# SPLIT4.net
KiCad netlist of a schematic drawn in Altium Designer
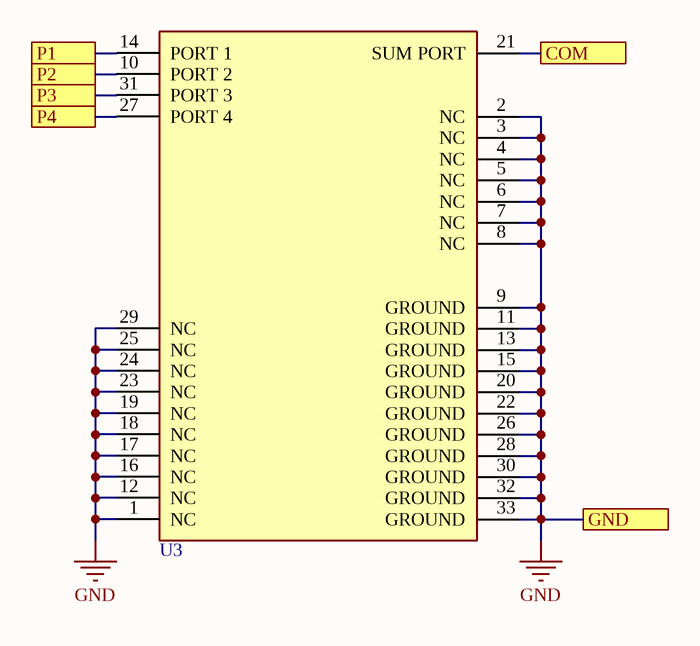
[diagram p0: SPLIT4.SchDoc]

(export (version "E")
  (design (tool "Eeschema 10.0.6"))
  (components
    (comp (ref "U3")
      (value "EP4RKU+")
      (footprint "EP4RKU+")
      (description "Power Splitter/Combiner 4 Way-0° 50Ω DC to 18 GHz")
      (libsource (lib "FullyDigital") (part "EP4RKU+"))
    )
  )
  (nets
    (net (code "1") (name "/COM") (class "Default")
      (node (ref "U3") (pin "21") (pinfunction "SUM_PORT_21") (pintype "passive"))
    )
    (net (code "2") (name "/P1") (class "Default")
      (node (ref "U3") (pin "14") (pinfunction "PORT_1_14") (pintype "passive"))
    )
    (net (code "3") (name "/P2") (class "Default")
      (node (ref "U3") (pin "10") (pinfunction "PORT_2_10") (pintype "passive"))
    )
    (net (code "4") (name "/P3") (class "Default")
      (node (ref "U3") (pin "31") (pinfunction "PORT_3_31") (pintype "passive"))
    )
    (net (code "5") (name "/P4") (class "Default")
      (node (ref "U3") (pin "27") (pinfunction "PORT_4_27") (pintype "passive"))
    )
    (net (code "6") (name "GND") (class "Default")
      (node (ref "U3") (pin "1") (pinfunction "NC_1") (pintype "passive"))
      (node (ref "U3") (pin "11") (pinfunction "GROUND_11") (pintype "power_in"))
      (node (ref "U3") (pin "12") (pinfunction "NC_12") (pintype "passive"))
      (node (ref "U3") (pin "13") (pinfunction "GROUND_13") (pintype "power_in"))
      (node (ref "U3") (pin "15") (pinfunction "GROUND_15") (pintype "power_in"))
      (node (ref "U3") (pin "16") (pinfunction "NC_16") (pintype "passive"))
      (node (ref "U3") (pin "17") (pinfunction "NC_17") (pintype "passive"))
      (node (ref "U3") (pin "18") (pinfunction "NC_18") (pintype "passive"))
      (node (ref "U3") (pin "19") (pinfunction "NC_19") (pintype "passive"))
      (node (ref "U3") (pin "2") (pinfunction "NC_2") (pintype "passive"))
      (node (ref "U3") (pin "20") (pinfunction "GROUND_20") (pintype "power_in"))
      (node (ref "U3") (pin "22") (pinfunction "GROUND_22") (pintype "power_in"))
      (node (ref "U3") (pin "23") (pinfunction "NC_23") (pintype "passive"))
      (node (ref "U3") (pin "24") (pinfunction "NC_24") (pintype "passive"))
      (node (ref "U3") (pin "25") (pinfunction "NC_25") (pintype "passive"))
      (node (ref "U3") (pin "26") (pinfunction "GROUND_26") (pintype "power_in"))
      (node (ref "U3") (pin "28") (pinfunction "GROUND_28") (pintype "power_in"))
      (node (ref "U3") (pin "29") (pinfunction "NC_29") (pintype "passive"))
      (node (ref "U3") (pin "3") (pinfunction "NC_3") (pintype "passive"))
      (node (ref "U3") (pin "30") (pinfunction "GROUND_30") (pintype "power_in"))
      (node (ref "U3") (pin "32") (pinfunction "GROUND_32") (pintype "power_in"))
      (node (ref "U3") (pin "33") (pinfunction "GROUND_33") (pintype "power_in"))
      (node (ref "U3") (pin "4") (pinfunction "NC_4") (pintype "passive"))
      (node (ref "U3") (pin "5") (pinfunction "NC_5") (pintype "passive"))
      (node (ref "U3") (pin "6") (pinfunction "NC_6") (pintype "passive"))
      (node (ref "U3") (pin "7") (pinfunction "NC_7") (pintype "passive"))
      (node (ref "U3") (pin "8") (pinfunction "NC_8") (pintype "passive"))
      (node (ref "U3") (pin "9") (pinfunction "GROUND_9") (pintype "power_in"))
    )
  )
)
